# old.net
KiCad netlist of a schematic drawn in EAGLE
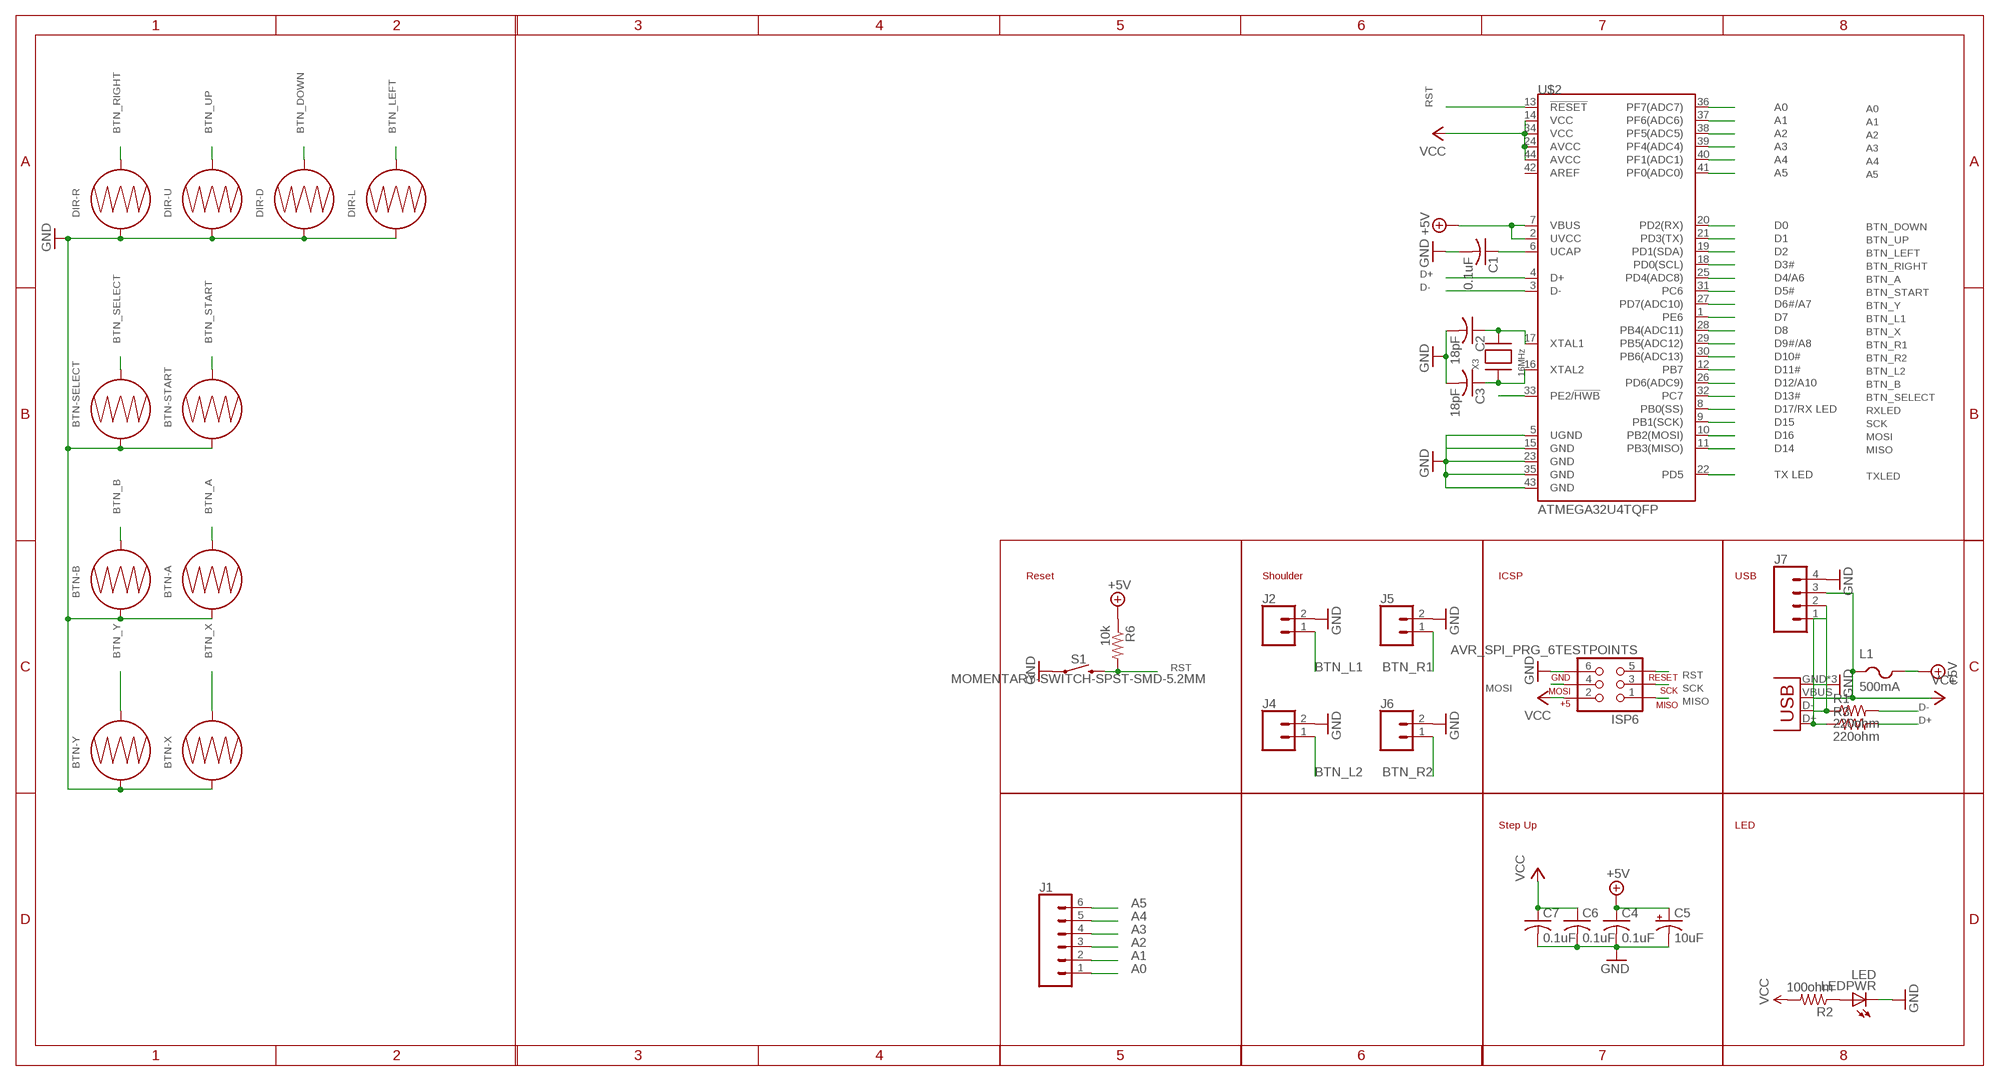
[diagram p0: schematic, sheet 1]

(export (version "E")
  (design (tool "Eeschema 10.0.6"))
  (components
    (comp (ref "BTN-A")
      (value "BUTTON-CONDUCTIVESMD")
      (footprint "eagle-import:BUTTON-CONDUCTIVE")
      (libsource (lib "eagle-import") (part "BUTTON-CONDUCTIVESMD"))
    )
    (comp (ref "BTN-B")
      (value "BUTTON-CONDUCTIVESMD")
      (footprint "eagle-import:BUTTON-CONDUCTIVE")
      (libsource (lib "eagle-import") (part "BUTTON-CONDUCTIVESMD"))
    )
    (comp (ref "BTN-SELECT")
      (value "BUTTON-CONDUCTIVESMD")
      (footprint "eagle-import:BUTTON-CONDUCTIVE")
      (libsource (lib "eagle-import") (part "BUTTON-CONDUCTIVESMD"))
    )
    (comp (ref "BTN-START")
      (value "BUTTON-CONDUCTIVESMD")
      (footprint "eagle-import:BUTTON-CONDUCTIVE")
      (libsource (lib "eagle-import") (part "BUTTON-CONDUCTIVESMD"))
    )
    (comp (ref "BTN-X")
      (value "BUTTON-CONDUCTIVESMD")
      (footprint "eagle-import:BUTTON-CONDUCTIVE")
      (libsource (lib "eagle-import") (part "BUTTON-CONDUCTIVESMD"))
    )
    (comp (ref "BTN-Y")
      (value "BUTTON-CONDUCTIVESMD")
      (footprint "eagle-import:BUTTON-CONDUCTIVE")
      (libsource (lib "eagle-import") (part "BUTTON-CONDUCTIVESMD"))
    )
    (comp (ref "C1")
      (value "0.1uF")
      (footprint "eagle-import:C0805")
      (libsource (lib "eagle-import") (part "C-USC0805"))
    )
    (comp (ref "C2")
      (value "18pF")
      (footprint "eagle-import:C0805")
      (libsource (lib "eagle-import") (part "C-USC0805"))
    )
    (comp (ref "C3")
      (value "18pF")
      (footprint "eagle-import:C0805")
      (libsource (lib "eagle-import") (part "C-USC0805"))
    )
    (comp (ref "C4")
      (value "0.1uF")
      (footprint "eagle-import:C0805")
      (libsource (lib "eagle-import") (part "C-USC0805"))
    )
    (comp (ref "C5")
      (value "10uF")
      (footprint "eagle-import:EIA3216")
      (libsource (lib "eagle-import") (part "10UF-TANT"))
    )
    (comp (ref "C6")
      (value "0.1uF")
      (footprint "eagle-import:C0805")
      (libsource (lib "eagle-import") (part "C-USC0805"))
    )
    (comp (ref "C7")
      (value "0.1uF")
      (footprint "eagle-import:C0805")
      (libsource (lib "eagle-import") (part "C-USC0805"))
    )
    (comp (ref "CN1")
      (value "USB-MICROB")
      (footprint "eagle-import:USB-MICROB")
      (libsource (lib "eagle-import") (part "USB-MICROB"))
    )
    (comp (ref "DIR-D")
      (value "BUTTON-CONDUCTIVESMD")
      (footprint "eagle-import:BUTTON-CONDUCTIVE")
      (libsource (lib "eagle-import") (part "BUTTON-CONDUCTIVESMD"))
    )
    (comp (ref "DIR-L")
      (value "BUTTON-CONDUCTIVESMD")
      (footprint "eagle-import:BUTTON-CONDUCTIVE")
      (libsource (lib "eagle-import") (part "BUTTON-CONDUCTIVESMD"))
    )
    (comp (ref "DIR-R")
      (value "BUTTON-CONDUCTIVESMD")
      (footprint "eagle-import:BUTTON-CONDUCTIVE")
      (libsource (lib "eagle-import") (part "BUTTON-CONDUCTIVESMD"))
    )
    (comp (ref "DIR-U")
      (value "BUTTON-CONDUCTIVESMD")
      (footprint "eagle-import:BUTTON-CONDUCTIVE")
      (libsource (lib "eagle-import") (part "BUTTON-CONDUCTIVESMD"))
    )
    (comp (ref "ISP6")
      (value "AVR_SPI_PRG_6TESTPOINTS")
      (footprint "eagle-import:2X3_TEST_POINTS")
      (libsource (lib "eagle-import") (part "AVR_SPI_PRG_6TESTPOINTS"))
    )
    (comp (ref "J1")
      (value "CONN_06NO_SILK_FEMALE_PTH")
      (footprint "eagle-import:1X06_NO_SILK")
      (libsource (lib "eagle-import") (part "CONN_06NO_SILK_FEMALE_PTH"))
    )
    (comp (ref "J2")
      (value "CONN_021X02_NO_SILK")
      (footprint "eagle-import:1X02_NO_SILK")
      (libsource (lib "eagle-import") (part "CONN_021X02_NO_SILK"))
    )
    (comp (ref "J4")
      (value "CONN_021X02_NO_SILK")
      (footprint "eagle-import:1X02_NO_SILK")
      (libsource (lib "eagle-import") (part "CONN_021X02_NO_SILK"))
    )
    (comp (ref "J5")
      (value "CONN_021X02_NO_SILK")
      (footprint "eagle-import:1X02_NO_SILK")
      (libsource (lib "eagle-import") (part "CONN_021X02_NO_SILK"))
    )
    (comp (ref "J6")
      (value "CONN_021X02_NO_SILK")
      (footprint "eagle-import:1X02_NO_SILK")
      (libsource (lib "eagle-import") (part "CONN_021X02_NO_SILK"))
    )
    (comp (ref "J7")
      (value "CONN_041X04_NO_SILK")
      (footprint "eagle-import:1X04_NO_SILK")
      (libsource (lib "eagle-import") (part "CONN_041X04_NO_SILK"))
    )
    (comp (ref "L1")
      (value "500mA")
      (footprint "eagle-import:R1206")
      (libsource (lib "eagle-import") (part "PTCFUSE-1206"))
    )
    (comp (ref "LEDPWR")
      (value "LED")
      (footprint "eagle-import:CHIPLED_0805")
      (libsource (lib "eagle-import") (part "LEDCHIPLED_0805"))
    )
    (comp (ref "R1")
      (value "220ohm")
      (footprint "eagle-import:R0805")
      (libsource (lib "eagle-import") (part "R-US_R0805"))
    )
    (comp (ref "R2")
      (value "100ohm")
      (footprint "eagle-import:R0805")
      (libsource (lib "eagle-import") (part "R-US_R0805"))
    )
    (comp (ref "R3")
      (value "220ohm")
      (footprint "eagle-import:R0805")
      (libsource (lib "eagle-import") (part "R-US_R0805"))
    )
    (comp (ref "R6")
      (value "10k")
      (footprint "eagle-import:R0805")
      (libsource (lib "eagle-import") (part "R-US_R0805"))
    )
    (comp (ref "S1")
      (value "MOMENTARY-SWITCH-SPST-SMD-5.2MM")
      (footprint "eagle-import:TACTILE_SWITCH_SMD_5.2MM")
      (libsource (lib "eagle-import") (part "MOMENTARY-SWITCH-SPST-SMD-5.2MM"))
    )
    (comp (ref "U$2")
      (value "ATMEGA32U4TQFP")
      (footprint "eagle-import:SPARKFUN-DIGITALIC_TQFP44")
      (libsource (lib "eagle-import") (part "ATMEGA32U4TQFP"))
    )
    (comp (ref "X3")
      (value "16MHz")
      (footprint "eagle-import:NX5032")
      (libsource (lib "eagle-import") (part "XTALNX5032"))
    )
  )
  (nets
    (net (code "1") (name "+5V") (class "Default")
      (node (ref "C4") (pin "1") (pinfunction "1_1") (pintype "passive"))
      (node (ref "C5") (pin "A") (pinfunction "+_A") (pintype "passive"))
      (node (ref "L1") (pin "2") (pinfunction "2_2") (pintype "passive"))
      (node (ref "R6") (pin "1") (pinfunction "1_1") (pintype "passive"))
      (node (ref "U$2") (pin "2") (pinfunction "UVCC_2") (pintype "bidirectional"))
      (node (ref "U$2") (pin "7") (pinfunction "VBUS_7") (pintype "bidirectional"))
    )
    (net (code "2") (name "/A0") (class "Default")
      (node (ref "J1") (pin "1") (pinfunction "1_1") (pintype "passive"))
      (node (ref "U$2") (pin "36") (pinfunction "PF7(ADC7)_36") (pintype "bidirectional"))
    )
    (net (code "3") (name "/A1") (class "Default")
      (node (ref "J1") (pin "2") (pinfunction "2_2") (pintype "passive"))
      (node (ref "U$2") (pin "37") (pinfunction "PF6(ADC6)_37") (pintype "bidirectional"))
    )
    (net (code "4") (name "/A2") (class "Default")
      (node (ref "J1") (pin "3") (pinfunction "3_3") (pintype "passive"))
      (node (ref "U$2") (pin "38") (pinfunction "PF5(ADC5)_38") (pintype "bidirectional"))
    )
    (net (code "5") (name "/A3") (class "Default")
      (node (ref "J1") (pin "4") (pinfunction "4_4") (pintype "passive"))
      (node (ref "U$2") (pin "39") (pinfunction "PF4(ADC4)_39") (pintype "bidirectional"))
    )
    (net (code "6") (name "/A4") (class "Default")
      (node (ref "J1") (pin "5") (pinfunction "5_5") (pintype "passive"))
      (node (ref "U$2") (pin "40") (pinfunction "PF1(ADC1)_40") (pintype "bidirectional"))
    )
    (net (code "7") (name "/A5") (class "Default")
      (node (ref "J1") (pin "6") (pinfunction "6_6") (pintype "passive"))
      (node (ref "U$2") (pin "41") (pinfunction "PF0(ADC0)_41") (pintype "bidirectional"))
    )
    (net (code "8") (name "/BTN_A") (class "Default")
      (node (ref "BTN-A") (pin "2") (pinfunction "2_2") (pintype "passive"))
      (node (ref "U$2") (pin "25") (pinfunction "PD4(ADC8)_25") (pintype "bidirectional"))
    )
    (net (code "9") (name "/BTN_B") (class "Default")
      (node (ref "BTN-B") (pin "2") (pinfunction "2_2") (pintype "passive"))
      (node (ref "U$2") (pin "26") (pinfunction "PD6(ADC9)_26") (pintype "bidirectional"))
    )
    (net (code "10") (name "/BTN_DOWN") (class "Default")
      (node (ref "DIR-D") (pin "2") (pinfunction "2_2") (pintype "passive"))
      (node (ref "U$2") (pin "20") (pinfunction "PD2(RX)_20") (pintype "bidirectional"))
    )
    (net (code "11") (name "/BTN_L1") (class "Default")
      (node (ref "J2") (pin "1") (pinfunction "1_1") (pintype "passive"))
      (node (ref "U$2") (pin "1") (pinfunction "PE6_1") (pintype "bidirectional"))
    )
    (net (code "12") (name "/BTN_L2") (class "Default")
      (node (ref "J4") (pin "1") (pinfunction "1_1") (pintype "passive"))
      (node (ref "U$2") (pin "12") (pinfunction "PB7_12") (pintype "bidirectional"))
    )
    (net (code "13") (name "/BTN_LEFT") (class "Default")
      (node (ref "DIR-L") (pin "2") (pinfunction "2_2") (pintype "passive"))
      (node (ref "U$2") (pin "19") (pinfunction "PD1(SDA)_19") (pintype "bidirectional"))
    )
    (net (code "14") (name "/BTN_R1") (class "Default")
      (node (ref "J5") (pin "1") (pinfunction "1_1") (pintype "passive"))
      (node (ref "U$2") (pin "29") (pinfunction "PB5(ADC12)_29") (pintype "bidirectional"))
    )
    (net (code "15") (name "/BTN_R2") (class "Default")
      (node (ref "J6") (pin "1") (pinfunction "1_1") (pintype "passive"))
      (node (ref "U$2") (pin "30") (pinfunction "PB6(ADC13)_30") (pintype "bidirectional"))
    )
    (net (code "16") (name "/BTN_RIGHT") (class "Default")
      (node (ref "DIR-R") (pin "2") (pinfunction "2_2") (pintype "passive"))
      (node (ref "U$2") (pin "18") (pinfunction "PD0(SCL)_18") (pintype "bidirectional"))
    )
    (net (code "17") (name "/BTN_SELECT") (class "Default")
      (node (ref "BTN-SELECT") (pin "2") (pinfunction "2_2") (pintype "passive"))
      (node (ref "U$2") (pin "32") (pinfunction "PC7_32") (pintype "bidirectional"))
    )
    (net (code "18") (name "/BTN_START") (class "Default")
      (node (ref "BTN-START") (pin "2") (pinfunction "2_2") (pintype "passive"))
      (node (ref "U$2") (pin "31") (pinfunction "PC6_31") (pintype "bidirectional"))
    )
    (net (code "19") (name "/BTN_UP") (class "Default")
      (node (ref "DIR-U") (pin "2") (pinfunction "2_2") (pintype "passive"))
      (node (ref "U$2") (pin "21") (pinfunction "PD3(TX)_21") (pintype "bidirectional"))
    )
    (net (code "20") (name "/BTN_X") (class "Default")
      (node (ref "BTN-X") (pin "2") (pinfunction "2_2") (pintype "passive"))
      (node (ref "U$2") (pin "28") (pinfunction "PB4(ADC11)_28") (pintype "bidirectional"))
    )
    (net (code "21") (name "/BTN_Y") (class "Default")
      (node (ref "BTN-Y") (pin "2") (pinfunction "2_2") (pintype "passive"))
      (node (ref "U$2") (pin "27") (pinfunction "PD7(ADC10)_27") (pintype "bidirectional"))
    )
    (net (code "22") (name "/D+") (class "Default")
      (node (ref "R3") (pin "2") (pinfunction "2_2") (pintype "passive"))
      (node (ref "U$2") (pin "4") (pinfunction "D+_4") (pintype "bidirectional"))
    )
    (net (code "23") (name "/D-") (class "Default")
      (node (ref "R1") (pin "2") (pinfunction "2_2") (pintype "passive"))
      (node (ref "U$2") (pin "3") (pinfunction "D-_3") (pintype "bidirectional"))
    )
    (net (code "24") (name "/MISO") (class "Default")
      (node (ref "ISP6") (pin "1") (pinfunction "1_1") (pintype "passive"))
      (node (ref "U$2") (pin "11") (pinfunction "PB3(MISO)_11") (pintype "bidirectional"))
    )
    (net (code "25") (name "/MOSI") (class "Default")
      (node (ref "ISP6") (pin "4") (pinfunction "4_4") (pintype "passive"))
      (node (ref "U$2") (pin "10") (pinfunction "PB2(MOSI)_10") (pintype "bidirectional"))
    )
    (net (code "26") (name "/RST") (class "Default")
      (node (ref "ISP6") (pin "5") (pinfunction "5_5") (pintype "passive"))
      (node (ref "R6") (pin "2") (pinfunction "2_2") (pintype "passive"))
      (node (ref "S1") (pin "3") (pinfunction "2_3") (pintype "passive"))
      (node (ref "U$2") (pin "13") (pinfunction "~{RESET}_13") (pintype "bidirectional"))
    )
    (net (code "27") (name "/RXLED") (class "Default")
      (node (ref "U$2") (pin "8") (pinfunction "PB0(SS)_8") (pintype "bidirectional"))
    )
    (net (code "28") (name "/SCK") (class "Default")
      (node (ref "ISP6") (pin "3") (pinfunction "3_3") (pintype "passive"))
      (node (ref "U$2") (pin "9") (pinfunction "PB1(SCK)_9") (pintype "bidirectional"))
    )
    (net (code "29") (name "/TXLED") (class "Default")
      (node (ref "U$2") (pin "22") (pinfunction "PD5_22") (pintype "bidirectional"))
    )
    (net (code "30") (name "GND") (class "Default")
      (node (ref "BTN-A") (pin "1") (pinfunction "1_1") (pintype "passive"))
      (node (ref "BTN-B") (pin "1") (pinfunction "1_1") (pintype "passive"))
      (node (ref "BTN-SELECT") (pin "1") (pinfunction "1_1") (pintype "passive"))
      (node (ref "BTN-START") (pin "1") (pinfunction "1_1") (pintype "passive"))
      (node (ref "BTN-X") (pin "1") (pinfunction "1_1") (pintype "passive"))
      (node (ref "BTN-Y") (pin "1") (pinfunction "1_1") (pintype "passive"))
      (node (ref "C1") (pin "2") (pinfunction "2_2") (pintype "passive"))
      (node (ref "C2") (pin "2") (pinfunction "2_2") (pintype "passive"))
      (node (ref "C3") (pin "2") (pinfunction "2_2") (pintype "passive"))
      (node (ref "C4") (pin "2") (pinfunction "2_2") (pintype "passive"))
      (node (ref "C5") (pin "C") (pinfunction "-_C") (pintype "passive"))
      (node (ref "C6") (pin "2") (pinfunction "2_2") (pintype "passive"))
      (node (ref "C7") (pin "2") (pinfunction "2_2") (pintype "passive"))
      (node (ref "CN1") (pin "GND") (pinfunction "GND_GND") (pintype "bidirectional"))
      (node (ref "CN1") (pin "MT1") (pinfunction "GND_MT1") (pintype "bidirectional"))
      (node (ref "CN1") (pin "MT2") (pinfunction "GND_MT2") (pintype "bidirectional"))
      (node (ref "DIR-D") (pin "1") (pinfunction "1_1") (pintype "passive"))
      (node (ref "DIR-L") (pin "1") (pinfunction "1_1") (pintype "passive"))
      (node (ref "DIR-R") (pin "1") (pinfunction "1_1") (pintype "passive"))
      (node (ref "DIR-U") (pin "1") (pinfunction "1_1") (pintype "passive"))
      (node (ref "ISP6") (pin "6") (pinfunction "6_6") (pintype "passive"))
      (node (ref "J2") (pin "2") (pinfunction "2_2") (pintype "passive"))
      (node (ref "J4") (pin "2") (pinfunction "2_2") (pintype "passive"))
      (node (ref "J5") (pin "2") (pinfunction "2_2") (pintype "passive"))
      (node (ref "J6") (pin "2") (pinfunction "2_2") (pintype "passive"))
      (node (ref "J7") (pin "4") (pinfunction "4_4") (pintype "passive"))
      (node (ref "LEDPWR") (pin "C") (pinfunction "C_C") (pintype "passive"))
      (node (ref "S1") (pin "1") (pinfunction "1_1") (pintype "passive"))
      (node (ref "U$2") (pin "15") (pinfunction "GND_15") (pintype "bidirectional"))
      (node (ref "U$2") (pin "23") (pinfunction "GND_23") (pintype "bidirectional"))
      (node (ref "U$2") (pin "35") (pinfunction "GND_35") (pintype "bidirectional"))
      (node (ref "U$2") (pin "43") (pinfunction "GND_43") (pintype "bidirectional"))
      (node (ref "U$2") (pin "5") (pinfunction "UGND_5") (pintype "bidirectional"))
    )
    (net (code "31") (name "Net-(CN1-PadD+)") (class "Default")
      (node (ref "CN1") (pin "D+") (pinfunction "D+_D+") (pintype "bidirectional"))
      (node (ref "J7") (pin "1") (pinfunction "1_1") (pintype "passive"))
      (node (ref "R3") (pin "1") (pinfunction "1_1") (pintype "passive"))
    )
    (net (code "32") (name "Net-(CN1-PadD-)") (class "Default")
      (node (ref "CN1") (pin "D-") (pinfunction "D-_D-") (pintype "bidirectional"))
      (node (ref "J7") (pin "2") (pinfunction "2_2") (pintype "passive"))
      (node (ref "R1") (pin "1") (pinfunction "1_1") (pintype "passive"))
    )
    (net (code "33") (name "Net-(LEDPWR-PadA)") (class "Default")
      (node (ref "LEDPWR") (pin "A") (pinfunction "A_A") (pintype "passive"))
      (node (ref "R2") (pin "1") (pinfunction "1_1") (pintype "passive"))
    )
    (net (code "34") (name "Net-(U$2-UCAP)") (class "Default")
      (node (ref "C1") (pin "1") (pinfunction "1_1") (pintype "passive"))
      (node (ref "U$2") (pin "6") (pinfunction "UCAP_6") (pintype "bidirectional"))
    )
    (net (code "35") (name "Net-(U$2-XTAL1)") (class "Default")
      (node (ref "C2") (pin "1") (pinfunction "1_1") (pintype "passive"))
      (node (ref "U$2") (pin "17") (pinfunction "XTAL1_17") (pintype "bidirectional"))
      (node (ref "X3") (pin "P$2") (pinfunction "P$2_P$2") (pintype "bidirectional"))
    )
    (net (code "36") (name "Net-(U$2-XTAL2)") (class "Default")
      (node (ref "C3") (pin "1") (pinfunction "1_1") (pintype "passive"))
      (node (ref "U$2") (pin "16") (pinfunction "XTAL2_16") (pintype "bidirectional"))
      (node (ref "X3") (pin "P$1") (pinfunction "P$1_P$1") (pintype "bidirectional"))
    )
    (net (code "37") (name "VCC") (class "Default")
      (node (ref "C6") (pin "1") (pinfunction "1_1") (pintype "passive"))
      (node (ref "C7") (pin "1") (pinfunction "1_1") (pintype "passive"))
      (node (ref "CN1") (pin "VBUS") (pinfunction "VBUS_VBUS") (pintype "bidirectional"))
      (node (ref "ISP6") (pin "2") (pinfunction "2_2") (pintype "passive"))
      (node (ref "J7") (pin "3") (pinfunction "3_3") (pintype "passive"))
      (node (ref "L1") (pin "1") (pinfunction "1_1") (pintype "passive"))
      (node (ref "R2") (pin "2") (pinfunction "2_2") (pintype "passive"))
      (node (ref "U$2") (pin "14") (pinfunction "VCC_14") (pintype "bidirectional"))
      (node (ref "U$2") (pin "24") (pinfunction "AVCC_24") (pintype "bidirectional"))
      (node (ref "U$2") (pin "34") (pinfunction "VCC_34") (pintype "bidirectional"))
      (node (ref "U$2") (pin "44") (pinfunction "AVCC_44") (pintype "bidirectional"))
    )
    (net (code "38") (name "unconnected-(U$2-AREF-Pad42)") (class "Default")
      (node (ref "U$2") (pin "42") (pinfunction "AREF_42") (pintype "bidirectional"))
    )
    (net (code "39") (name "unconnected-(U$2-PE2{slash}~{HWB}-Pad33)") (class "Default")
      (node (ref "U$2") (pin "33") (pinfunction "PE2/~{HWB}_33") (pintype "bidirectional"))
    )
  )
)
